# LKS_0311.net
KiCad netlist of a schematic drawn in Altium Designer
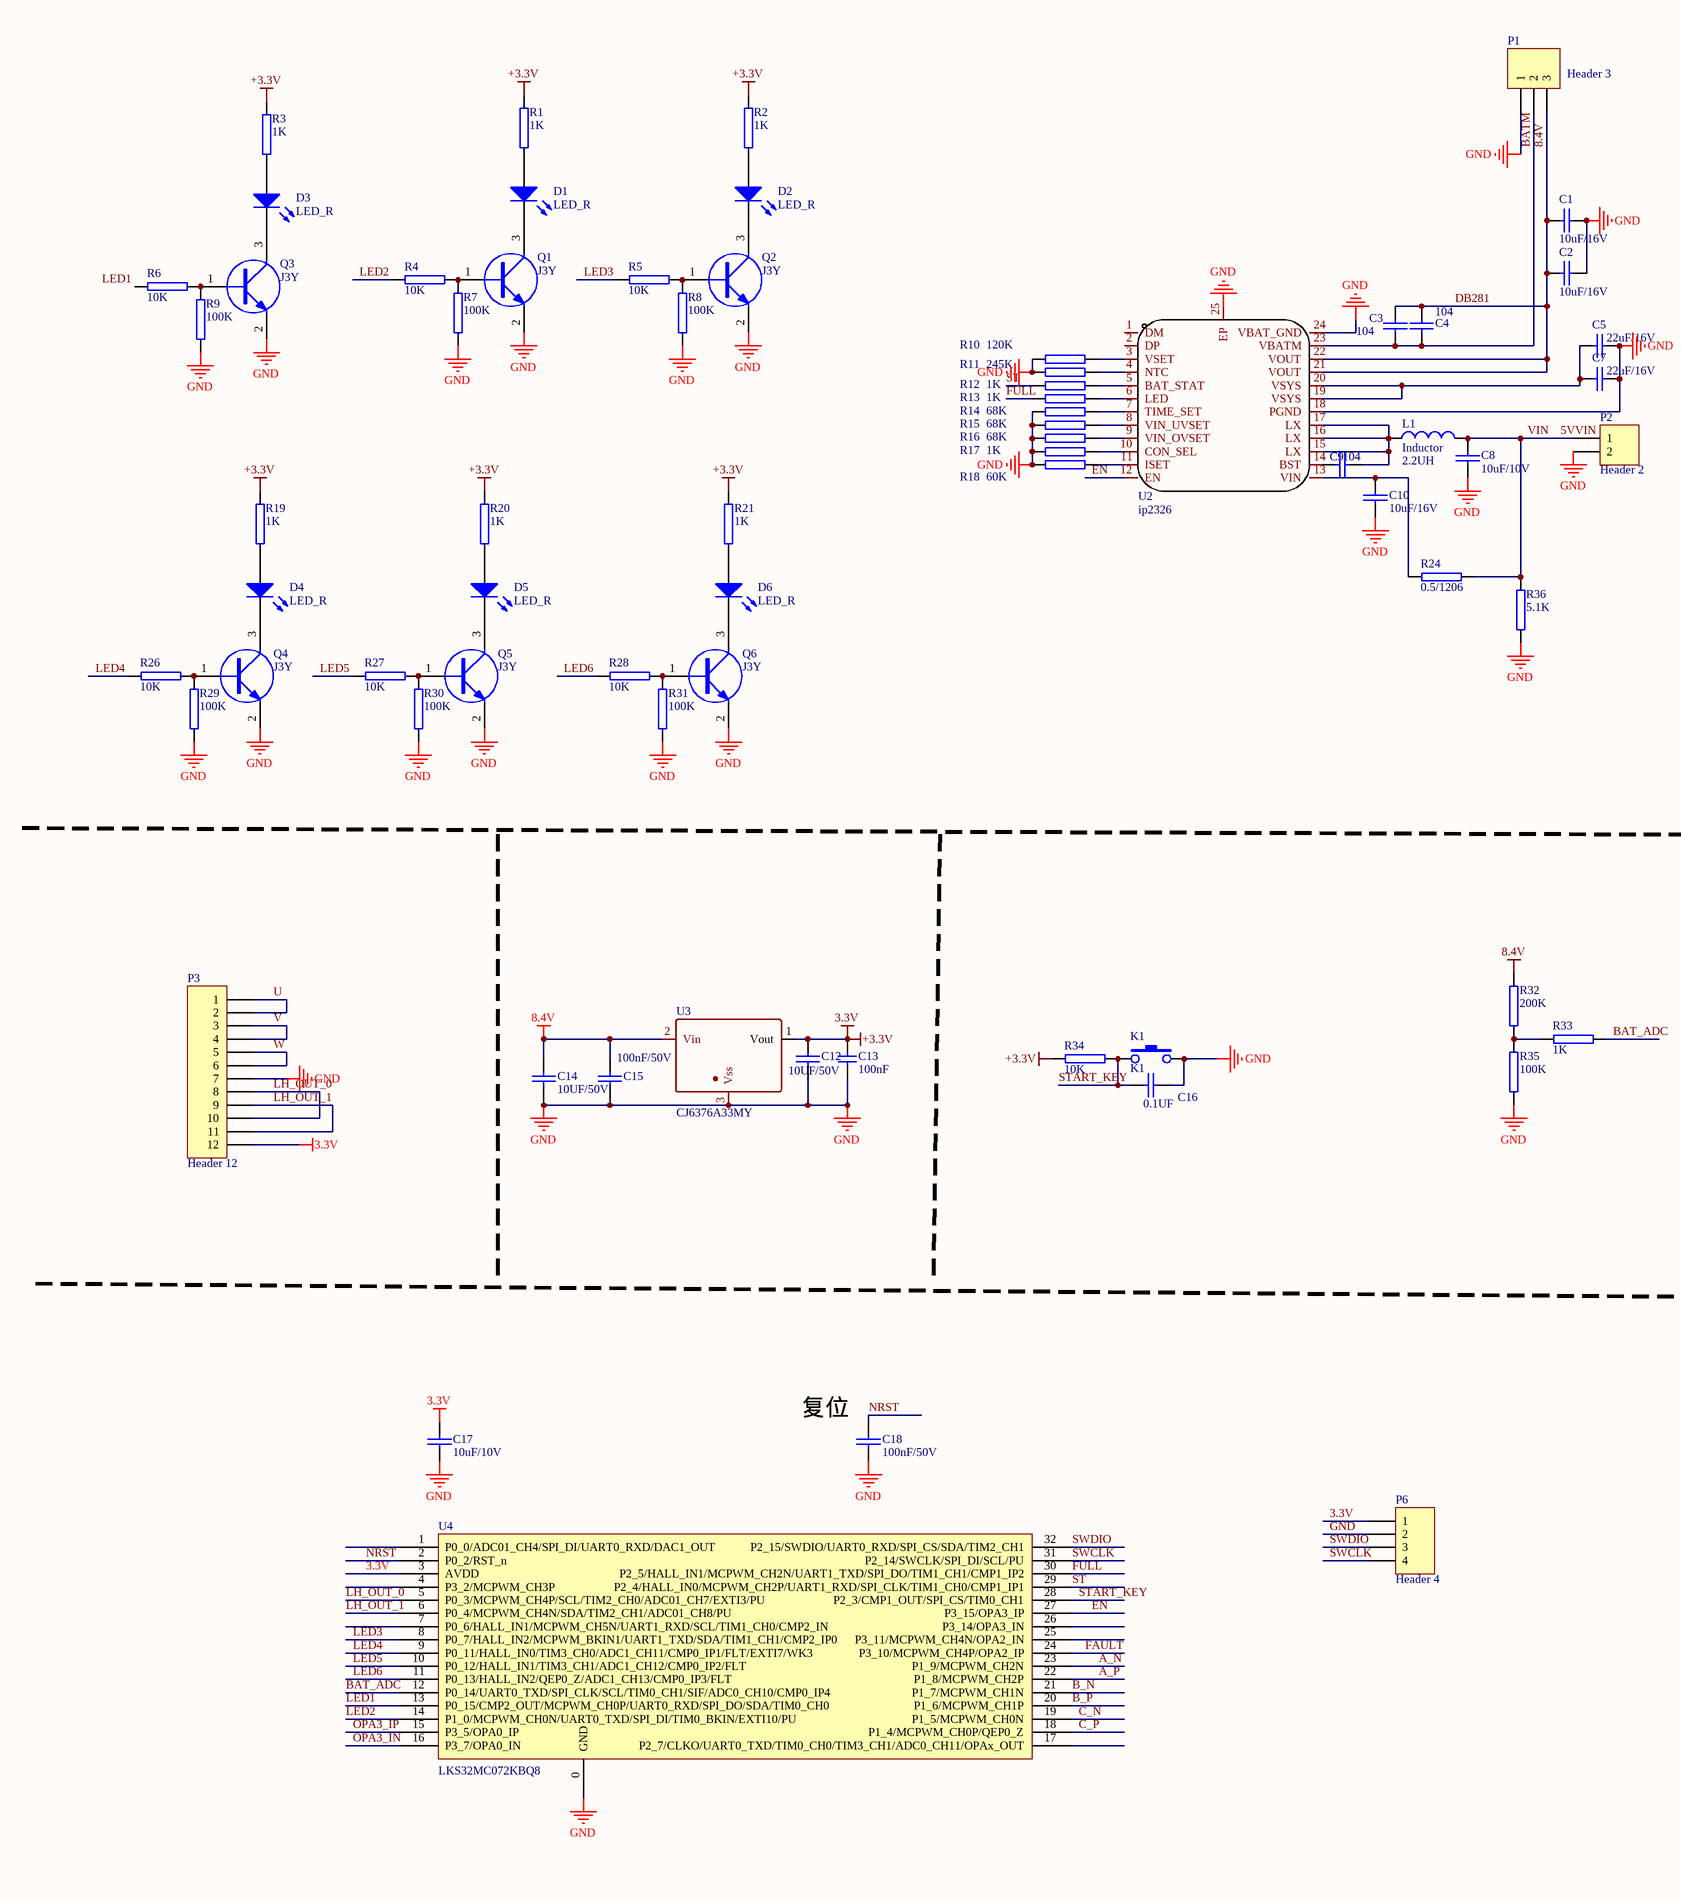
[diagram p0: LKS_0311.SchDoc, left]
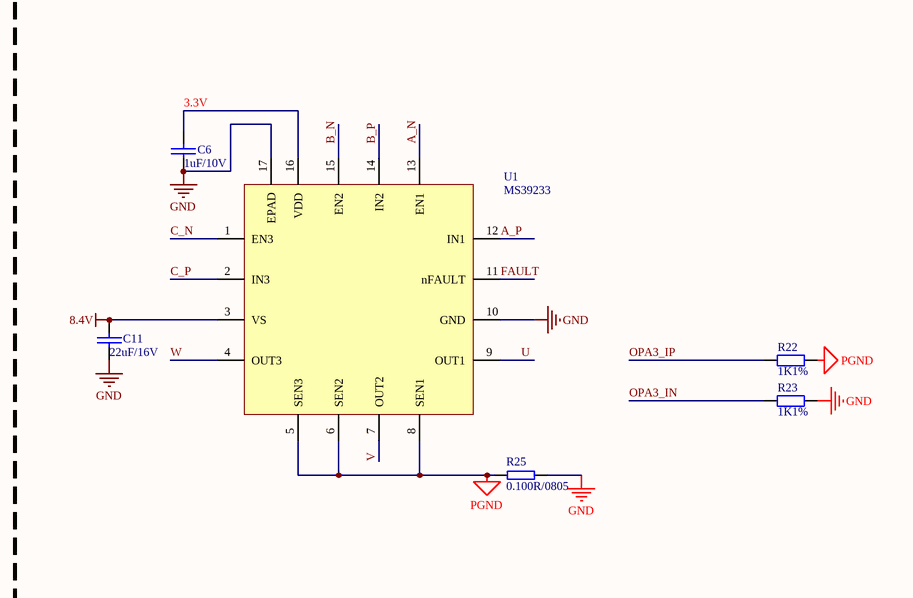
[diagram p1: LKS_0311.SchDoc, right]

(export (version "E")
  (design (tool "Eeschema 10.0.6"))
  (components
    (comp (ref "C1")
      (value "10uF/16V")
      (footprint "C 0402_M")
      (description "Capacitor")
      (libsource (lib "*") (part "C"))
    )
    (comp (ref "C2")
      (value "10uF/16V")
      (footprint "C 0402_M")
      (description "Capacitor")
      (libsource (lib "*") (part "C"))
    )
    (comp (ref "C3")
      (value "104")
      (footprint "C 0402_M")
      (description "Capacitor")
      (libsource (lib "*") (part "C"))
    )
    (comp (ref "C4")
      (value "104")
      (footprint "C 0402_M")
      (description "Capacitor")
      (libsource (lib "*") (part "C"))
    )
    (comp (ref "C5")
      (value "22uF/16V")
      (footprint "C 0402_M")
      (description "Capacitor")
      (libsource (lib "*") (part "C"))
    )
    (comp (ref "C6")
      (value "1uF/10V")
      (footprint "C 0402_M")
      (description "Capacitor")
      (libsource (lib "*") (part "C"))
    )
    (comp (ref "C7")
      (value "22uF/16V")
      (footprint "C 0402_M")
      (description "Capacitor")
      (libsource (lib "*") (part "C"))
    )
    (comp (ref "C8")
      (value "10uF/10V")
      (footprint "C 0402_M")
      (description "Capacitor")
      (libsource (lib "*") (part "C"))
    )
    (comp (ref "C9")
      (value "104")
      (footprint "C 0402_M")
      (description "Capacitor")
      (libsource (lib "*") (part "C"))
    )
    (comp (ref "C10")
      (value "10uF/16V")
      (footprint "C 0402_M")
      (description "Capacitor")
      (libsource (lib "*") (part "C"))
    )
    (comp (ref "C11")
      (value "22uF/16V")
      (footprint "C 0805_M")
      (description "Capacitor")
      (libsource (lib "*") (part "C"))
    )
    (comp (ref "C12")
      (value "10UF/50V")
      (footprint "0805C")
      (description "Capacitor")
      (libsource (lib "*") (part "CAP"))
    )
    (comp (ref "C13") (value "100nF") (footprint "0402") (libsource (lib "") (part "CAP_1")))
    (comp (ref "C14")
      (value "10UF/50V")
      (footprint "0805C")
      (description "Capacitor")
      (libsource (lib "*") (part "CAP"))
    )
    (comp (ref "C15")
      (value "100nF/50V")
      (footprint "0402")
      (description "Capacitor")
      (libsource (lib "*") (part "CAP"))
    )
    (comp (ref "C16")
      (value "0.1UF")
      (footprint "0603_RON")
      (description "Capacitor")
      (libsource (lib "STM32f401_8261_LIB") (part "CAP"))
    )
    (comp (ref "C17")
      (value "10uF/10V")
      (footprint "C 0402_M")
      (description "Capacitor")
      (libsource (lib "*") (part "C"))
    )
    (comp (ref "C18")
      (value "100nF/50V")
      (footprint "C 0402_M")
      (description "Capacitor")
      (libsource (lib "*") (part "C"))
    )
    (comp (ref "D1") (value "LED_R") (footprint "SMDLED") (libsource (lib "PuXun1") (part "LED")))
    (comp (ref "D2") (value "LED_R") (footprint "SMDLED") (libsource (lib "PuXun1") (part "LED")))
    (comp (ref "D3") (value "LED_R") (footprint "SMDLED") (libsource (lib "PuXun1") (part "LED")))
    (comp (ref "D4") (value "LED_R") (footprint "SMDLED") (libsource (lib "PuXun1") (part "LED")))
    (comp (ref "D5") (value "LED_R") (footprint "SMDLED") (libsource (lib "PuXun1") (part "LED")))
    (comp (ref "D6") (value "LED_R") (footprint "SMDLED") (libsource (lib "PuXun1") (part "LED")))
    (comp (ref "K1") (value "K1") (footprint "Button3x4x2") (libsource (lib "SCHLIB_NEW") (part "K1")))
    (comp (ref "L1")
      (value "Inductor")
      (footprint "0402-A")
      (fields (field (name "ALTIUM_VALUE") "2.2UH") (field (name "PUBLISHER") "Altium Limited"))
      (libsource (lib "Miscellaneous Devices") (part "Inductor"))
    )
    (comp (ref "P1")
      (value "Header 3")
      (footprint "HDR1X3")
      (description "Header, 3-Pin")
      (fields (field (name "PUBLISHER") "Altium Limited"))
      (libsource (lib "Miscellaneous Connectors") (part "Header 3"))
    )
    (comp (ref "P2")
      (value "Header 2")
      (footprint "HDR1X2")
      (description "Header, 2-Pin")
      (fields (field (name "PUBLISHER") "Altium Limited"))
      (libsource (lib "Miscellaneous Connectors") (part "Header 2"))
    )
    (comp (ref "P3")
      (value "Header 12")
      (footprint "SMD-12")
      (description "Header, 12-Pin")
      (fields (field (name "PUBLISHER") "Altium Limited"))
      (libsource (lib "Miscellaneous Connectors") (part "Header 12"))
    )
    (comp (ref "P6")
      (value "Header 4")
      (footprint "HDR1X4")
      (description "Header, 4-Pin")
      (fields (field (name "PUBLISHER") "Altium Limited"))
      (libsource (lib "Miscellaneous Connectors") (part "Header 4"))
    )
    (comp (ref "Q1")
      (value "J3Y")
      (footprint "SOT-23")
      (description "NPN Transistor")
      (libsource (lib "*") (part "NPN"))
    )
    (comp (ref "Q2")
      (value "J3Y")
      (footprint "SOT-23")
      (description "NPN Transistor")
      (libsource (lib "*") (part "NPN"))
    )
    (comp (ref "Q3")
      (value "J3Y")
      (footprint "SOT-23")
      (description "NPN Transistor")
      (libsource (lib "*") (part "NPN"))
    )
    (comp (ref "Q4")
      (value "J3Y")
      (footprint "SOT-23")
      (description "NPN Transistor")
      (libsource (lib "*") (part "NPN"))
    )
    (comp (ref "Q5")
      (value "J3Y")
      (footprint "SOT-23")
      (description "NPN Transistor")
      (libsource (lib "*") (part "NPN"))
    )
    (comp (ref "Q6")
      (value "J3Y")
      (footprint "SOT-23")
      (description "NPN Transistor")
      (libsource (lib "*") (part "NPN"))
    )
    (comp (ref "R1") (value "1K") (footprint "0603_RON") (libsource (lib "*") (part "RES2_S")))
    (comp (ref "R2") (value "1K") (footprint "0603_RON") (libsource (lib "*") (part "RES2_S")))
    (comp (ref "R3") (value "1K") (footprint "0603_RON") (libsource (lib "*") (part "RES2_S")))
    (comp (ref "R4") (value "10K") (footprint "0603_RON") (libsource (lib "*") (part "RES2_S")))
    (comp (ref "R5") (value "10K") (footprint "0603_RON") (libsource (lib "*") (part "RES2_S")))
    (comp (ref "R6") (value "10K") (footprint "0603_RON") (libsource (lib "*") (part "RES2_S")))
    (comp (ref "R7") (value "100K") (footprint "0603_RON") (libsource (lib "*") (part "RES2_S")))
    (comp (ref "R8") (value "100K") (footprint "0603_RON") (libsource (lib "*") (part "RES2_S")))
    (comp (ref "R9") (value "100K") (footprint "0603_RON") (libsource (lib "*") (part "RES2_S")))
    (comp (ref "R10") (value "120K") (footprint "0603_RON") (libsource (lib "*") (part "RES2_S")))
    (comp (ref "R11") (value "245K") (footprint "0603_RON") (libsource (lib "*") (part "RES2_S")))
    (comp (ref "R12") (value "1K") (footprint "0603_RON") (libsource (lib "*") (part "RES2_S")))
    (comp (ref "R13") (value "1K") (footprint "0603_RON") (libsource (lib "*") (part "RES2_S")))
    (comp (ref "R14") (value "68K") (footprint "0603_RON") (libsource (lib "*") (part "RES2_S")))
    (comp (ref "R15") (value "68K") (footprint "0603_RON") (libsource (lib "*") (part "RES2_S")))
    (comp (ref "R16") (value "68K") (footprint "0603_RON") (libsource (lib "*") (part "RES2_S")))
    (comp (ref "R17") (value "1K") (footprint "0603_RON") (libsource (lib "*") (part "RES2_S")))
    (comp (ref "R18") (value "60K") (footprint "0603_RON") (libsource (lib "*") (part "RES2_S")))
    (comp (ref "R19") (value "1K") (footprint "0603_RON") (libsource (lib "*") (part "RES2_S")))
    (comp (ref "R20") (value "1K") (footprint "0603_RON") (libsource (lib "*") (part "RES2_S")))
    (comp (ref "R21") (value "1K") (footprint "0603_RON") (libsource (lib "*") (part "RES2_S")))
    (comp (ref "R22")
      (value "1K1%")
      (footprint "R 0402_M")
      (description "Resistor")
      (fields (field (name "PUBLISHER") "Altium Limited"))
      (libsource (lib "LINKO_V1.0") (part "Res"))
    )
    (comp (ref "R23")
      (value "1K1%")
      (footprint "R 0402_M")
      (description "Resistor")
      (fields (field (name "PUBLISHER") "Altium Limited"))
      (libsource (lib "LINKO_V1.0") (part "Res"))
    )
    (comp (ref "R24") (value "0.5/1206") (footprint "0603_RON") (libsource (lib "*") (part "RES2_S")))
    (comp (ref "R25") (value "0.100R/0805") (footprint "R 0805_M") (libsource (lib "*") (part "RES2短")))
    (comp (ref "R26") (value "10K") (footprint "0603_RON") (libsource (lib "*") (part "RES2_S")))
    (comp (ref "R27") (value "10K") (footprint "0603_RON") (libsource (lib "*") (part "RES2_S")))
    (comp (ref "R28") (value "10K") (footprint "0603_RON") (libsource (lib "*") (part "RES2_S")))
    (comp (ref "R29") (value "100K") (footprint "0603_RON") (libsource (lib "*") (part "RES2_S")))
    (comp (ref "R30") (value "100K") (footprint "0603_RON") (libsource (lib "*") (part "RES2_S")))
    (comp (ref "R31") (value "100K") (footprint "0603_RON") (libsource (lib "*") (part "RES2_S")))
    (comp (ref "R32") (value "200K") (footprint "0603_RON") (libsource (lib "*") (part "RES2_S")))
    (comp (ref "R33") (value "1K") (footprint "0603_RON") (libsource (lib "*") (part "RES2_S")))
    (comp (ref "R34") (value "10K") (footprint "0603_RON") (libsource (lib "*") (part "RES2_S")))
    (comp (ref "R35") (value "100K") (footprint "0603_RON") (libsource (lib "*") (part "RES2_S")))
    (comp (ref "R36") (value "5.1K") (footprint "0603_RON") (libsource (lib "*") (part "RES2_S")))
    (comp (ref "U1") (value "MS39233") (footprint "QFN16") (libsource (lib "Schlib1") (part "MS39233")))
    (comp (ref "U2") (value "ip2326") (libsource (lib "LKS034DO_Motor_0520_1") (part "ip2326")))
    (comp (ref "U3")
      (value "CJ6376A33MY")
      (footprint "SOT89-3")
      (libsource (lib "LKS034DO_Motor_0520_1") (part "78L15"))
    )
    (comp (ref "U4")
      (value "LKS32MC072KBQ8")
      (footprint "QFN32 5x5_M")
      (description "LKS32MC072KBQ8\r\n凌鸥创芯，128KFlash，12KRAM")
      (libsource (lib "LINKO_V1.1") (part "LKS32MC072KBQ82"))
    )
  )
  (nets
    (net (code "1") (name "+3.3V") (class "Default")
      (node (ref "C12") (pin "2") (pinfunction "2_2") (pintype "passive"))
      (node (ref "C13") (pin "1") (pinfunction "1_1") (pintype "passive"))
      (node (ref "C17") (pin "2") (pinfunction "2_2") (pintype "passive"))
      (node (ref "C6") (pin "2") (pinfunction "2_2") (pintype "passive"))
      (node (ref "P3") (pin "12") (pinfunction "12_12") (pintype "passive"))
      (node (ref "P6") (pin "1") (pinfunction "1_1") (pintype "passive"))
      (node (ref "R1") (pin "2") (pinfunction "2_2") (pintype "passive"))
      (node (ref "R19") (pin "2") (pinfunction "2_2") (pintype "passive"))
      (node (ref "R2") (pin "2") (pinfunction "2_2") (pintype "passive"))
      (node (ref "R20") (pin "2") (pinfunction "2_2") (pintype "passive"))
      (node (ref "R21") (pin "2") (pinfunction "2_2") (pintype "passive"))
      (node (ref "R3") (pin "2") (pinfunction "2_2") (pintype "passive"))
      (node (ref "R34") (pin "2") (pinfunction "2_2") (pintype "passive"))
      (node (ref "U1") (pin "16") (pinfunction "VDD_16") (pintype "passive"))
      (node (ref "U3") (pin "1") (pinfunction "Vout_1") (pintype "passive"))
      (node (ref "U4") (pin "3") (pinfunction "AVDD_3") (pintype "passive"))
    )
    (net (code "2") (name "/5VVIN") (class "Default")
      (node (ref "C8") (pin "1") (pinfunction "1_1") (pintype "passive"))
      (node (ref "L1") (pin "2") (pinfunction "2_2") (pintype "passive"))
      (node (ref "P2") (pin "1") (pinfunction "1_1") (pintype "passive"))
      (node (ref "R24") (pin "1") (pinfunction "1_1") (pintype "passive"))
      (node (ref "R36") (pin "1") (pinfunction "1_1") (pintype "passive"))
    )
    (net (code "3") (name "/A_N") (class "Default")
      (node (ref "U1") (pin "13") (pinfunction "EN1_13") (pintype "passive"))
      (node (ref "U4") (pin "23") (pinfunction "P1_9/MCPWM_CH2N_23") (pintype "passive"))
    )
    (net (code "4") (name "/A_P") (class "Default")
      (node (ref "U1") (pin "12") (pinfunction "IN1_12") (pintype "passive"))
      (node (ref "U4") (pin "22") (pinfunction "P1_8/MCPWM_CH2P_22") (pintype "passive"))
    )
    (net (code "5") (name "/BATM") (class "Default")
      (node (ref "C3") (pin "1") (pinfunction "1_1") (pintype "passive"))
      (node (ref "C4") (pin "2") (pinfunction "2_2") (pintype "passive"))
      (node (ref "P1") (pin "2") (pinfunction "2_2") (pintype "passive"))
      (node (ref "U2") (pin "23") (pinfunction "VBATM_23") (pintype "passive"))
    )
    (net (code "6") (name "/BAT_ADC") (class "Default")
      (node (ref "R33") (pin "1") (pinfunction "1_1") (pintype "passive"))
      (node (ref "U4") (pin "12") (pinfunction "P0_14/UART0_TXD/SPI_CLK/SCL/TIM0_CH1/SIF/ADC0_CH10/CMP0_IP4_12") (pintype "passive"))
    )
    (net (code "7") (name "/B_N") (class "Default")
      (node (ref "U1") (pin "15") (pinfunction "EN2_15") (pintype "passive"))
      (node (ref "U4") (pin "21") (pinfunction "P1_7/MCPWM_CH1N_21") (pintype "passive"))
    )
    (net (code "8") (name "/B_P") (class "Default")
      (node (ref "U1") (pin "14") (pinfunction "IN2_14") (pintype "passive"))
      (node (ref "U4") (pin "20") (pinfunction "P1_6/MCPWM_CH1P_20") (pintype "passive"))
    )
    (net (code "9") (name "/C_N") (class "Default")
      (node (ref "U1") (pin "1") (pinfunction "EN3_1") (pintype "passive"))
      (node (ref "U4") (pin "19") (pinfunction "P1_5/MCPWM_CH0N_19") (pintype "passive"))
    )
    (net (code "10") (name "/C_P") (class "Default")
      (node (ref "U1") (pin "2") (pinfunction "IN3_2") (pintype "passive"))
      (node (ref "U4") (pin "18") (pinfunction "P1_4/MCPWM_CH0P/QEP0_Z_18") (pintype "passive"))
    )
    (net (code "11") (name "/EN") (class "Default")
      (node (ref "U2") (pin "12") (pinfunction "EN_12") (pintype "passive"))
      (node (ref "U4") (pin "27") (pinfunction "P3_15/OPA3_IP_27") (pintype "passive"))
    )
    (net (code "12") (name "/FAULT") (class "Default")
      (node (ref "U1") (pin "11") (pinfunction "nFAULT_11") (pintype "passive"))
      (node (ref "U4") (pin "24") (pinfunction "P3_10/MCPWM_CH4P/OPA2_IP_24") (pintype "passive"))
    )
    (net (code "13") (name "/FULL") (class "Default")
      (node (ref "R13") (pin "2") (pinfunction "2_2") (pintype "passive"))
      (node (ref "U4") (pin "30") (pinfunction "P2_5/HALL_IN1/MCPWM_CH2N/UART1_TXD/SPI_DO/TIM1_CH1/CMP1_IP2_30") (pintype "passive"))
    )
    (net (code "14") (name "/LED1") (class "Default")
      (node (ref "U4") (pin "13") (pinfunction "P0_15/CMP2_OUT/MCPWM_CH0P/UART0_RXD/SPI_DO/SDA/TIM0_CH0_13") (pintype "passive"))
    )
    (net (code "15") (name "/LED2") (class "Default")
      (node (ref "R4") (pin "2") (pinfunction "2_2") (pintype "passive"))
      (node (ref "U4") (pin "14") (pinfunction "P1_0/MCPWM_CH0N/UART0_TXD/SPI_DI/TIM0_BKIN/EXTI10/PU_14") (pintype "passive"))
    )
    (net (code "16") (name "/LED3") (class "Default")
      (node (ref "R5") (pin "2") (pinfunction "2_2") (pintype "passive"))
      (node (ref "U4") (pin "8") (pinfunction "P0_7/HALL_IN2/MCPWM_BKIN1/UART1_TXD/SDA/TIM1_CH1/CMP2_IP0_8") (pintype "passive"))
    )
    (net (code "17") (name "/LED4") (class "Default")
      (node (ref "R26") (pin "2") (pinfunction "2_2") (pintype "passive"))
      (node (ref "U4") (pin "9") (pinfunction "P0_11/HALL_IN0/TIM3_CH0/ADC1_CH11/CMP0_IP1/FLT/EXTI7/WK3_9") (pintype "passive"))
    )
    (net (code "18") (name "/LED5") (class "Default")
      (node (ref "R27") (pin "2") (pinfunction "2_2") (pintype "passive"))
      (node (ref "U4") (pin "10") (pinfunction "P0_12/HALL_IN1/TIM3_CH1/ADC1_CH12/CMP0_IP2/FLT_10") (pintype "passive"))
    )
    (net (code "19") (name "/LED6") (class "Default")
      (node (ref "R28") (pin "2") (pinfunction "2_2") (pintype "passive"))
      (node (ref "U4") (pin "11") (pinfunction "P0_13/HALL_IN2/QEP0_Z/ADC1_CH13/CMP0_IP3/FLT_11") (pintype "passive"))
    )
    (net (code "20") (name "/LH_OUT_0") (class "Default")
      (node (ref "P3") (pin "10") (pinfunction "10_10") (pintype "passive"))
      (node (ref "P3") (pin "8") (pinfunction "8_8") (pintype "passive"))
      (node (ref "U4") (pin "5") (pinfunction "P0_3/MCPWM_CH4P/SCL/TIM2_CH0/ADC01_CH7/EXTI3/PU_5") (pintype "passive"))
    )
    (net (code "21") (name "/LH_OUT_1") (class "Default")
      (node (ref "P3") (pin "11") (pinfunction "11_11") (pintype "passive"))
      (node (ref "P3") (pin "9") (pinfunction "9_9") (pintype "passive"))
      (node (ref "U4") (pin "6") (pinfunction "P0_4/MCPWM_CH4N/SDA/TIM2_CH1/ADC01_CH8/PU_6") (pintype "passive"))
    )
    (net (code "22") (name "/NRST") (class "Default")
      (node (ref "C18") (pin "1") (pinfunction "1_1") (pintype "passive"))
      (node (ref "U4") (pin "2") (pinfunction "P0_2/RST_n_2") (pintype "passive"))
    )
    (net (code "23") (name "/OPA3_IN") (class "Default")
      (node (ref "R23") (pin "2") (pinfunction "2_2") (pintype "passive"))
      (node (ref "U4") (pin "16") (pinfunction "P3_7/OPA0_IN_16") (pintype "passive"))
    )
    (net (code "24") (name "/OPA3_IP") (class "Default")
      (node (ref "R22") (pin "2") (pinfunction "2_2") (pintype "passive"))
      (node (ref "U4") (pin "15") (pinfunction "P3_5/OPA0_IP_15") (pintype "passive"))
    )
    (net (code "25") (name "/ST") (class "Default")
      (node (ref "R12") (pin "2") (pinfunction "2_2") (pintype "passive"))
      (node (ref "U4") (pin "29") (pinfunction "P2_4/HALL_IN0/MCPWM_CH2P/UART1_RXD/SPI_CLK/TIM1_CH0/CMP1_IP1_29") (pintype "passive"))
    )
    (net (code "26") (name "/START_KEY") (class "Default")
      (node (ref "C16") (pin "1") (pinfunction "1_1") (pintype "passive"))
      (node (ref "K1") (pin "1") (pintype "passive"))
      (node (ref "R34") (pin "1") (pinfunction "1_1") (pintype "passive"))
      (node (ref "U4") (pin "28") (pinfunction "P2_3/CMP1_OUT/SPI_CS/TIM0_CH1_28") (pintype "passive"))
    )
    (net (code "27") (name "/SWCLK") (class "Default")
      (node (ref "P6") (pin "4") (pinfunction "4_4") (pintype "passive"))
      (node (ref "U4") (pin "31") (pinfunction "P2_14/SWCLK/SPI_DI/SCL/PU_31") (pintype "passive"))
    )
    (net (code "28") (name "/SWDIO") (class "Default")
      (node (ref "P6") (pin "3") (pinfunction "3_3") (pintype "passive"))
      (node (ref "U4") (pin "32") (pinfunction "P2_15/SWDIO/UART0_RXD/SPI_CS/SDA/TIM2_CH1_32") (pintype "passive"))
    )
    (net (code "29") (name "/U") (class "Default")
      (node (ref "P3") (pin "1") (pinfunction "1_1") (pintype "passive"))
      (node (ref "P3") (pin "2") (pinfunction "2_2") (pintype "passive"))
      (node (ref "U1") (pin "9") (pinfunction "OUT1_9") (pintype "passive"))
    )
    (net (code "30") (name "/V") (class "Default")
      (node (ref "P3") (pin "3") (pinfunction "3_3") (pintype "passive"))
      (node (ref "P3") (pin "4") (pinfunction "4_4") (pintype "passive"))
      (node (ref "U1") (pin "7") (pinfunction "OUT2_7") (pintype "passive"))
    )
    (net (code "31") (name "/W") (class "Default")
      (node (ref "P3") (pin "5") (pinfunction "5_5") (pintype "passive"))
      (node (ref "P3") (pin "6") (pinfunction "6_6") (pintype "passive"))
      (node (ref "U1") (pin "4") (pinfunction "OUT3_4") (pintype "passive"))
    )
    (net (code "32") (name "8.4V") (class "Default")
      (node (ref "C1") (pin "2") (pinfunction "2_2") (pintype "passive"))
      (node (ref "C11") (pin "2") (pinfunction "2_2") (pintype "passive"))
      (node (ref "C14") (pin "2") (pinfunction "2_2") (pintype "passive"))
      (node (ref "C15") (pin "1") (pinfunction "1_1") (pintype "passive"))
      (node (ref "C2") (pin "2") (pinfunction "2_2") (pintype "passive"))
      (node (ref "C3") (pin "2") (pinfunction "2_2") (pintype "passive"))
      (node (ref "C4") (pin "1") (pinfunction "1_1") (pintype "passive"))
      (node (ref "P1") (pin "3") (pinfunction "3_3") (pintype "passive"))
      (node (ref "R32") (pin "1") (pinfunction "1_1") (pintype "passive"))
      (node (ref "U1") (pin "3") (pinfunction "VS_3") (pintype "passive"))
      (node (ref "U2") (pin "21") (pinfunction "VOUT_21") (pintype "passive"))
      (node (ref "U2") (pin "22") (pinfunction "VOUT_22") (pintype "passive"))
      (node (ref "U3") (pin "2") (pinfunction "Vin_2") (pintype "passive"))
    )
    (net (code "33") (name "GND") (class "Default")
      (node (ref "C1") (pin "1") (pinfunction "1_1") (pintype "passive"))
      (node (ref "C10") (pin "2") (pinfunction "2_2") (pintype "passive"))
      (node (ref "C11") (pin "1") (pinfunction "1_1") (pintype "passive"))
      (node (ref "C12") (pin "1") (pinfunction "1_1") (pintype "passive"))
      (node (ref "C13") (pin "2") (pinfunction "2_2") (pintype "passive"))
      (node (ref "C14") (pin "1") (pinfunction "1_1") (pintype "passive"))
      (node (ref "C15") (pin "2") (pinfunction "2_2") (pintype "passive"))
      (node (ref "C16") (pin "2") (pinfunction "2_2") (pintype "passive"))
      (node (ref "C17") (pin "1") (pinfunction "1_1") (pintype "passive"))
      (node (ref "C18") (pin "2") (pinfunction "2_2") (pintype "passive"))
      (node (ref "C2") (pin "1") (pinfunction "1_1") (pintype "passive"))
      (node (ref "C5") (pin "1") (pinfunction "1_1") (pintype "passive"))
      (node (ref "C6") (pin "1") (pinfunction "1_1") (pintype "passive"))
      (node (ref "C7") (pin "1") (pinfunction "1_1") (pintype "passive"))
      (node (ref "C8") (pin "2") (pinfunction "2_2") (pintype "passive"))
      (node (ref "K1") (pin "2") (pintype "passive"))
      (node (ref "P1") (pin "1") (pinfunction "1_1") (pintype "passive"))
      (node (ref "P2") (pin "2") (pinfunction "2_2") (pintype "passive"))
      (node (ref "P3") (pin "7") (pinfunction "7_7") (pintype "passive"))
      (node (ref "P6") (pin "2") (pinfunction "2_2") (pintype "passive"))
      (node (ref "Q1") (pin "2") (pinfunction "E_2") (pintype "passive"))
      (node (ref "Q2") (pin "2") (pinfunction "E_2") (pintype "passive"))
      (node (ref "Q3") (pin "2") (pinfunction "E_2") (pintype "passive"))
      (node (ref "Q4") (pin "2") (pinfunction "E_2") (pintype "passive"))
      (node (ref "Q5") (pin "2") (pinfunction "E_2") (pintype "passive"))
      (node (ref "Q6") (pin "2") (pinfunction "E_2") (pintype "passive"))
      (node (ref "R10") (pin "2") (pinfunction "2_2") (pintype "passive"))
      (node (ref "R11") (pin "2") (pinfunction "2_2") (pintype "passive"))
      (node (ref "R14") (pin "2") (pinfunction "2_2") (pintype "passive"))
      (node (ref "R15") (pin "2") (pinfunction "2_2") (pintype "passive"))
      (node (ref "R16") (pin "2") (pinfunction "2_2") (pintype "passive"))
      (node (ref "R17") (pin "2") (pinfunction "2_2") (pintype "passive"))
      (node (ref "R18") (pin "2") (pinfunction "2_2") (pintype "passive"))
      (node (ref "R23") (pin "1") (pinfunction "1_1") (pintype "passive"))
      (node (ref "R25") (pin "2") (pinfunction "2_2") (pintype "passive"))
      (node (ref "R29") (pin "2") (pinfunction "2_2") (pintype "passive"))
      (node (ref "R30") (pin "2") (pinfunction "2_2") (pintype "passive"))
      (node (ref "R31") (pin "2") (pinfunction "2_2") (pintype "passive"))
      (node (ref "R35") (pin "2") (pinfunction "2_2") (pintype "passive"))
      (node (ref "R36") (pin "2") (pinfunction "2_2") (pintype "passive"))
      (node (ref "R7") (pin "2") (pinfunction "2_2") (pintype "passive"))
      (node (ref "R8") (pin "2") (pinfunction "2_2") (pintype "passive"))
      (node (ref "R9") (pin "2") (pinfunction "2_2") (pintype "passive"))
      (node (ref "U1") (pin "10") (pinfunction "GND_10") (pintype "passive"))
      (node (ref "U1") (pin "17") (pinfunction "EPAD_17") (pintype "passive"))
      (node (ref "U2") (pin "18") (pinfunction "PGND_18") (pintype "passive"))
      (node (ref "U2") (pin "24") (pinfunction "VBAT_GND_24") (pintype "passive"))
      (node (ref "U2") (pin "25") (pinfunction "EP_25") (pintype "passive"))
      (node (ref "U3") (pin "3") (pinfunction "Vss_3") (pintype "passive"))
      (node (ref "U4") (pin "0") (pinfunction "GND_0") (pintype "passive"))
    )
    (net (code "34") (name "Net-(C5-Pad2)") (class "Default")
      (node (ref "C5") (pin "2") (pinfunction "2_2") (pintype "passive"))
      (node (ref "C7") (pin "2") (pinfunction "2_2") (pintype "passive"))
      (node (ref "U2") (pin "19") (pinfunction "VSYS_19") (pintype "passive"))
      (node (ref "U2") (pin "20") (pinfunction "VSYS_20") (pintype "passive"))
    )
    (net (code "35") (name "Net-(C9-Pad2)") (class "Default")
      (node (ref "C9") (pin "2") (pinfunction "2_2") (pintype "passive"))
      (node (ref "L1") (pin "1") (pinfunction "1_1") (pintype "passive"))
      (node (ref "U2") (pin "15") (pinfunction "LX_15") (pintype "passive"))
      (node (ref "U2") (pin "16") (pinfunction "LX_16") (pintype "passive"))
      (node (ref "U2") (pin "17") (pinfunction "LX_17") (pintype "passive"))
    )
    (net (code "36") (name "Net-(D1-A)") (class "Default")
      (node (ref "D1") (pin "1") (pinfunction "A_1") (pintype "passive"))
      (node (ref "R1") (pin "1") (pinfunction "1_1") (pintype "passive"))
    )
    (net (code "37") (name "Net-(D1-K)") (class "Default")
      (node (ref "D1") (pin "2") (pinfunction "K_2") (pintype "passive"))
      (node (ref "Q1") (pin "3") (pinfunction "C_3") (pintype "passive"))
    )
    (net (code "38") (name "Net-(D2-A)") (class "Default")
      (node (ref "D2") (pin "1") (pinfunction "A_1") (pintype "passive"))
      (node (ref "R2") (pin "1") (pinfunction "1_1") (pintype "passive"))
    )
    (net (code "39") (name "Net-(D2-K)") (class "Default")
      (node (ref "D2") (pin "2") (pinfunction "K_2") (pintype "passive"))
      (node (ref "Q2") (pin "3") (pinfunction "C_3") (pintype "passive"))
    )
    (net (code "40") (name "Net-(D3-A)") (class "Default")
      (node (ref "D3") (pin "1") (pinfunction "A_1") (pintype "passive"))
      (node (ref "R3") (pin "1") (pinfunction "1_1") (pintype "passive"))
    )
    (net (code "41") (name "Net-(D3-K)") (class "Default")
      (node (ref "D3") (pin "2") (pinfunction "K_2") (pintype "passive"))
      (node (ref "Q3") (pin "3") (pinfunction "C_3") (pintype "passive"))
    )
    (net (code "42") (name "Net-(D4-A)") (class "Default")
      (node (ref "D4") (pin "1") (pinfunction "A_1") (pintype "passive"))
      (node (ref "R19") (pin "1") (pinfunction "1_1") (pintype "passive"))
    )
    (net (code "43") (name "Net-(D4-K)") (class "Default")
      (node (ref "D4") (pin "2") (pinfunction "K_2") (pintype "passive"))
      (node (ref "Q4") (pin "3") (pinfunction "C_3") (pintype "passive"))
    )
    (net (code "44") (name "Net-(D5-A)") (class "Default")
      (node (ref "D5") (pin "1") (pinfunction "A_1") (pintype "passive"))
      (node (ref "R20") (pin "1") (pinfunction "1_1") (pintype "passive"))
    )
    (net (code "45") (name "Net-(D5-K)") (class "Default")
      (node (ref "D5") (pin "2") (pinfunction "K_2") (pintype "passive"))
      (node (ref "Q5") (pin "3") (pinfunction "C_3") (pintype "passive"))
    )
    (net (code "46") (name "Net-(D6-A)") (class "Default")
      (node (ref "D6") (pin "1") (pinfunction "A_1") (pintype "passive"))
      (node (ref "R21") (pin "1") (pinfunction "1_1") (pintype "passive"))
    )
    (net (code "47") (name "Net-(D6-K)") (class "Default")
      (node (ref "D6") (pin "2") (pinfunction "K_2") (pintype "passive"))
      (node (ref "Q6") (pin "3") (pinfunction "C_3") (pintype "passive"))
    )
    (net (code "48") (name "Net-(Q1-B)") (class "Default")
      (node (ref "Q1") (pin "1") (pinfunction "B_1") (pintype "passive"))
      (node (ref "R4") (pin "1") (pinfunction "1_1") (pintype "passive"))
      (node (ref "R7") (pin "1") (pinfunction "1_1") (pintype "passive"))
    )
    (net (code "49") (name "Net-(Q2-B)") (class "Default")
      (node (ref "Q2") (pin "1") (pinfunction "B_1") (pintype "passive"))
      (node (ref "R5") (pin "1") (pinfunction "1_1") (pintype "passive"))
      (node (ref "R8") (pin "1") (pinfunction "1_1") (pintype "passive"))
    )
    (net (code "50") (name "Net-(Q3-B)") (class "Default")
      (node (ref "Q3") (pin "1") (pinfunction "B_1") (pintype "passive"))
      (node (ref "R6") (pin "1") (pinfunction "1_1") (pintype "passive"))
      (node (ref "R9") (pin "1") (pinfunction "1_1") (pintype "passive"))
    )
    (net (code "51") (name "Net-(Q4-B)") (class "Default")
      (node (ref "Q4") (pin "1") (pinfunction "B_1") (pintype "passive"))
      (node (ref "R26") (pin "1") (pinfunction "1_1") (pintype "passive"))
      (node (ref "R29") (pin "1") (pinfunction "1_1") (pintype "passive"))
    )
    (net (code "52") (name "Net-(Q5-B)") (class "Default")
      (node (ref "Q5") (pin "1") (pinfunction "B_1") (pintype "passive"))
      (node (ref "R27") (pin "1") (pinfunction "1_1") (pintype "passive"))
      (node (ref "R30") (pin "1") (pinfunction "1_1") (pintype "passive"))
    )
    (net (code "53") (name "Net-(Q6-B)") (class "Default")
      (node (ref "Q6") (pin "1") (pinfunction "B_1") (pintype "passive"))
      (node (ref "R28") (pin "1") (pinfunction "1_1") (pintype "passive"))
      (node (ref "R31") (pin "1") (pinfunction "1_1") (pintype "passive"))
    )
    (net (code "54") (name "Net-(R32-Pad2)") (class "Default")
      (node (ref "R32") (pin "2") (pinfunction "2_2") (pintype "passive"))
      (node (ref "R33") (pin "2") (pinfunction "2_2") (pintype "passive"))
      (node (ref "R35") (pin "1") (pinfunction "1_1") (pintype "passive"))
    )
    (net (code "55") (name "Net-(U2-BAT_STAT)") (class "Default")
      (node (ref "R12") (pin "1") (pinfunction "1_1") (pintype "passive"))
      (node (ref "U2") (pin "5") (pinfunction "BAT_STAT_5") (pintype "passive"))
    )
    (net (code "56") (name "Net-(U2-BST)") (class "Default")
      (node (ref "C9") (pin "1") (pinfunction "1_1") (pintype "passive"))
      (node (ref "U2") (pin "14") (pinfunction "BST_14") (pintype "passive"))
    )
    (net (code "57") (name "Net-(U2-CON_SEL)") (class "Default")
      (node (ref "R17") (pin "1") (pinfunction "1_1") (pintype "passive"))
      (node (ref "U2") (pin "10") (pinfunction "CON_SEL_10") (pintype "passive"))
    )
    (net (code "58") (name "Net-(U2-ISET)") (class "Default")
      (node (ref "R18") (pin "1") (pinfunction "1_1") (pintype "passive"))
      (node (ref "U2") (pin "11") (pinfunction "ISET_11") (pintype "passive"))
    )
    (net (code "59") (name "Net-(U2-LED)") (class "Default")
      (node (ref "R13") (pin "1") (pinfunction "1_1") (pintype "passive"))
      (node (ref "U2") (pin "6") (pinfunction "LED_6") (pintype "passive"))
    )
    (net (code "60") (name "Net-(U2-NTC)") (class "Default")
      (node (ref "R11") (pin "1") (pinfunction "1_1") (pintype "passive"))
      (node (ref "U2") (pin "4") (pinfunction "NTC_4") (pintype "passive"))
    )
    (net (code "61") (name "Net-(U2-TIME_SET)") (class "Default")
      (node (ref "R14") (pin "1") (pinfunction "1_1") (pintype "passive"))
      (node (ref "U2") (pin "7") (pinfunction "TIME_SET_7") (pintype "passive"))
    )
    (net (code "62") (name "Net-(U2-VIN)") (class "Default")
      (node (ref "C10") (pin "1") (pinfunction "1_1") (pintype "passive"))
      (node (ref "R24") (pin "2") (pinfunction "2_2") (pintype "passive"))
      (node (ref "U2") (pin "13") (pinfunction "VIN_13") (pintype "passive"))
    )
    (net (code "63") (name "Net-(U2-VIN_OVSET)") (class "Default")
      (node (ref "R16") (pin "1") (pinfunction "1_1") (pintype "passive"))
      (node (ref "U2") (pin "9") (pinfunction "VIN_OVSET_9") (pintype "passive"))
    )
    (net (code "64") (name "Net-(U2-VIN_UVSET)") (class "Default")
      (node (ref "R15") (pin "1") (pinfunction "1_1") (pintype "passive"))
      (node (ref "U2") (pin "8") (pinfunction "VIN_UVSET_8") (pintype "passive"))
    )
    (net (code "65") (name "Net-(U2-VSET)") (class "Default")
      (node (ref "R10") (pin "1") (pinfunction "1_1") (pintype "passive"))
      (node (ref "U2") (pin "3") (pinfunction "VSET_3") (pintype "passive"))
    )
    (net (code "66") (name "PGND") (class "Default")
      (node (ref "R22") (pin "1") (pinfunction "1_1") (pintype "passive"))
      (node (ref "R25") (pin "1") (pinfunction "1_1") (pintype "passive"))
      (node (ref "U1") (pin "5") (pinfunction "SEN3_5") (pintype "passive"))
      (node (ref "U1") (pin "6") (pinfunction "SEN2_6") (pintype "passive"))
      (node (ref "U1") (pin "8") (pinfunction "SEN1_8") (pintype "passive"))
    )
    (net (code "67") (name "unconnected-(R6-Pad2)") (class "Default")
      (node (ref "R6") (pin "2") (pinfunction "2_2") (pintype "passive"))
    )
    (net (code "68") (name "unconnected-(U2-DM-Pad1)") (class "Default")
      (node (ref "U2") (pin "1") (pinfunction "DM_1") (pintype "passive"))
    )
    (net (code "69") (name "unconnected-(U2-DP-Pad2)") (class "Default")
      (node (ref "U2") (pin "2") (pinfunction "DP_2") (pintype "passive"))
    )
    (net (code "70") (name "unconnected-(U4-P0_0{slash}ADC01_CH4{slash}SPI_DI{slash}UART0_RXD{slash}DAC1_OUT-Pad1)") (class "Default")
      (node (ref "U4") (pin "1") (pinfunction "P0_0/ADC01_CH4/SPI_DI/UART0_RXD/DAC1_OUT_1") (pintype "passive"))
    )
    (net (code "71") (name "unconnected-(U4-P0_6{slash}HALL_IN1{slash}MCPWM_CH5N{slash}UART1_RXD{slash}SCL{slash}TIM1_CH0{slash}CMP2_IN-Pad7)") (class "Default")
      (node (ref "U4") (pin "7") (pinfunction "P0_6/HALL_IN1/MCPWM_CH5N/UART1_RXD/SCL/TIM1_CH0/CMP2_IN_7") (pintype "passive"))
    )
    (net (code "72") (name "unconnected-(U4-P2_7{slash}CLKO{slash}UART0_TXD{slash}TIM0_CH0{slash}TIM3_CH1{slash}ADC0_CH11{slash}OPAx_OUT-Pad17)") (class "Default")
      (node (ref "U4") (pin "17") (pinfunction "P2_7/CLKO/UART0_TXD/TIM0_CH0/TIM3_CH1/ADC0_CH11/OPAx_OUT_17") (pintype "passive"))
    )
    (net (code "73") (name "unconnected-(U4-P3_2{slash}MCPWM_CH3P-Pad4)") (class "Default")
      (node (ref "U4") (pin "4") (pinfunction "P3_2/MCPWM_CH3P_4") (pintype "passive"))
    )
    (net (code "74") (name "unconnected-(U4-P3_11{slash}MCPWM_CH4N{slash}OPA2_IN-Pad25)") (class "Default")
      (node (ref "U4") (pin "25") (pinfunction "P3_11/MCPWM_CH4N/OPA2_IN_25") (pintype "passive"))
    )
    (net (code "75") (name "unconnected-(U4-P3_14{slash}OPA3_IN-Pad26)") (class "Default")
      (node (ref "U4") (pin "26") (pinfunction "P3_14/OPA3_IN_26") (pintype "passive"))
    )
  )
)
